# water_counter.net
KiCad netlist of a schematic drawn in EasyEDA
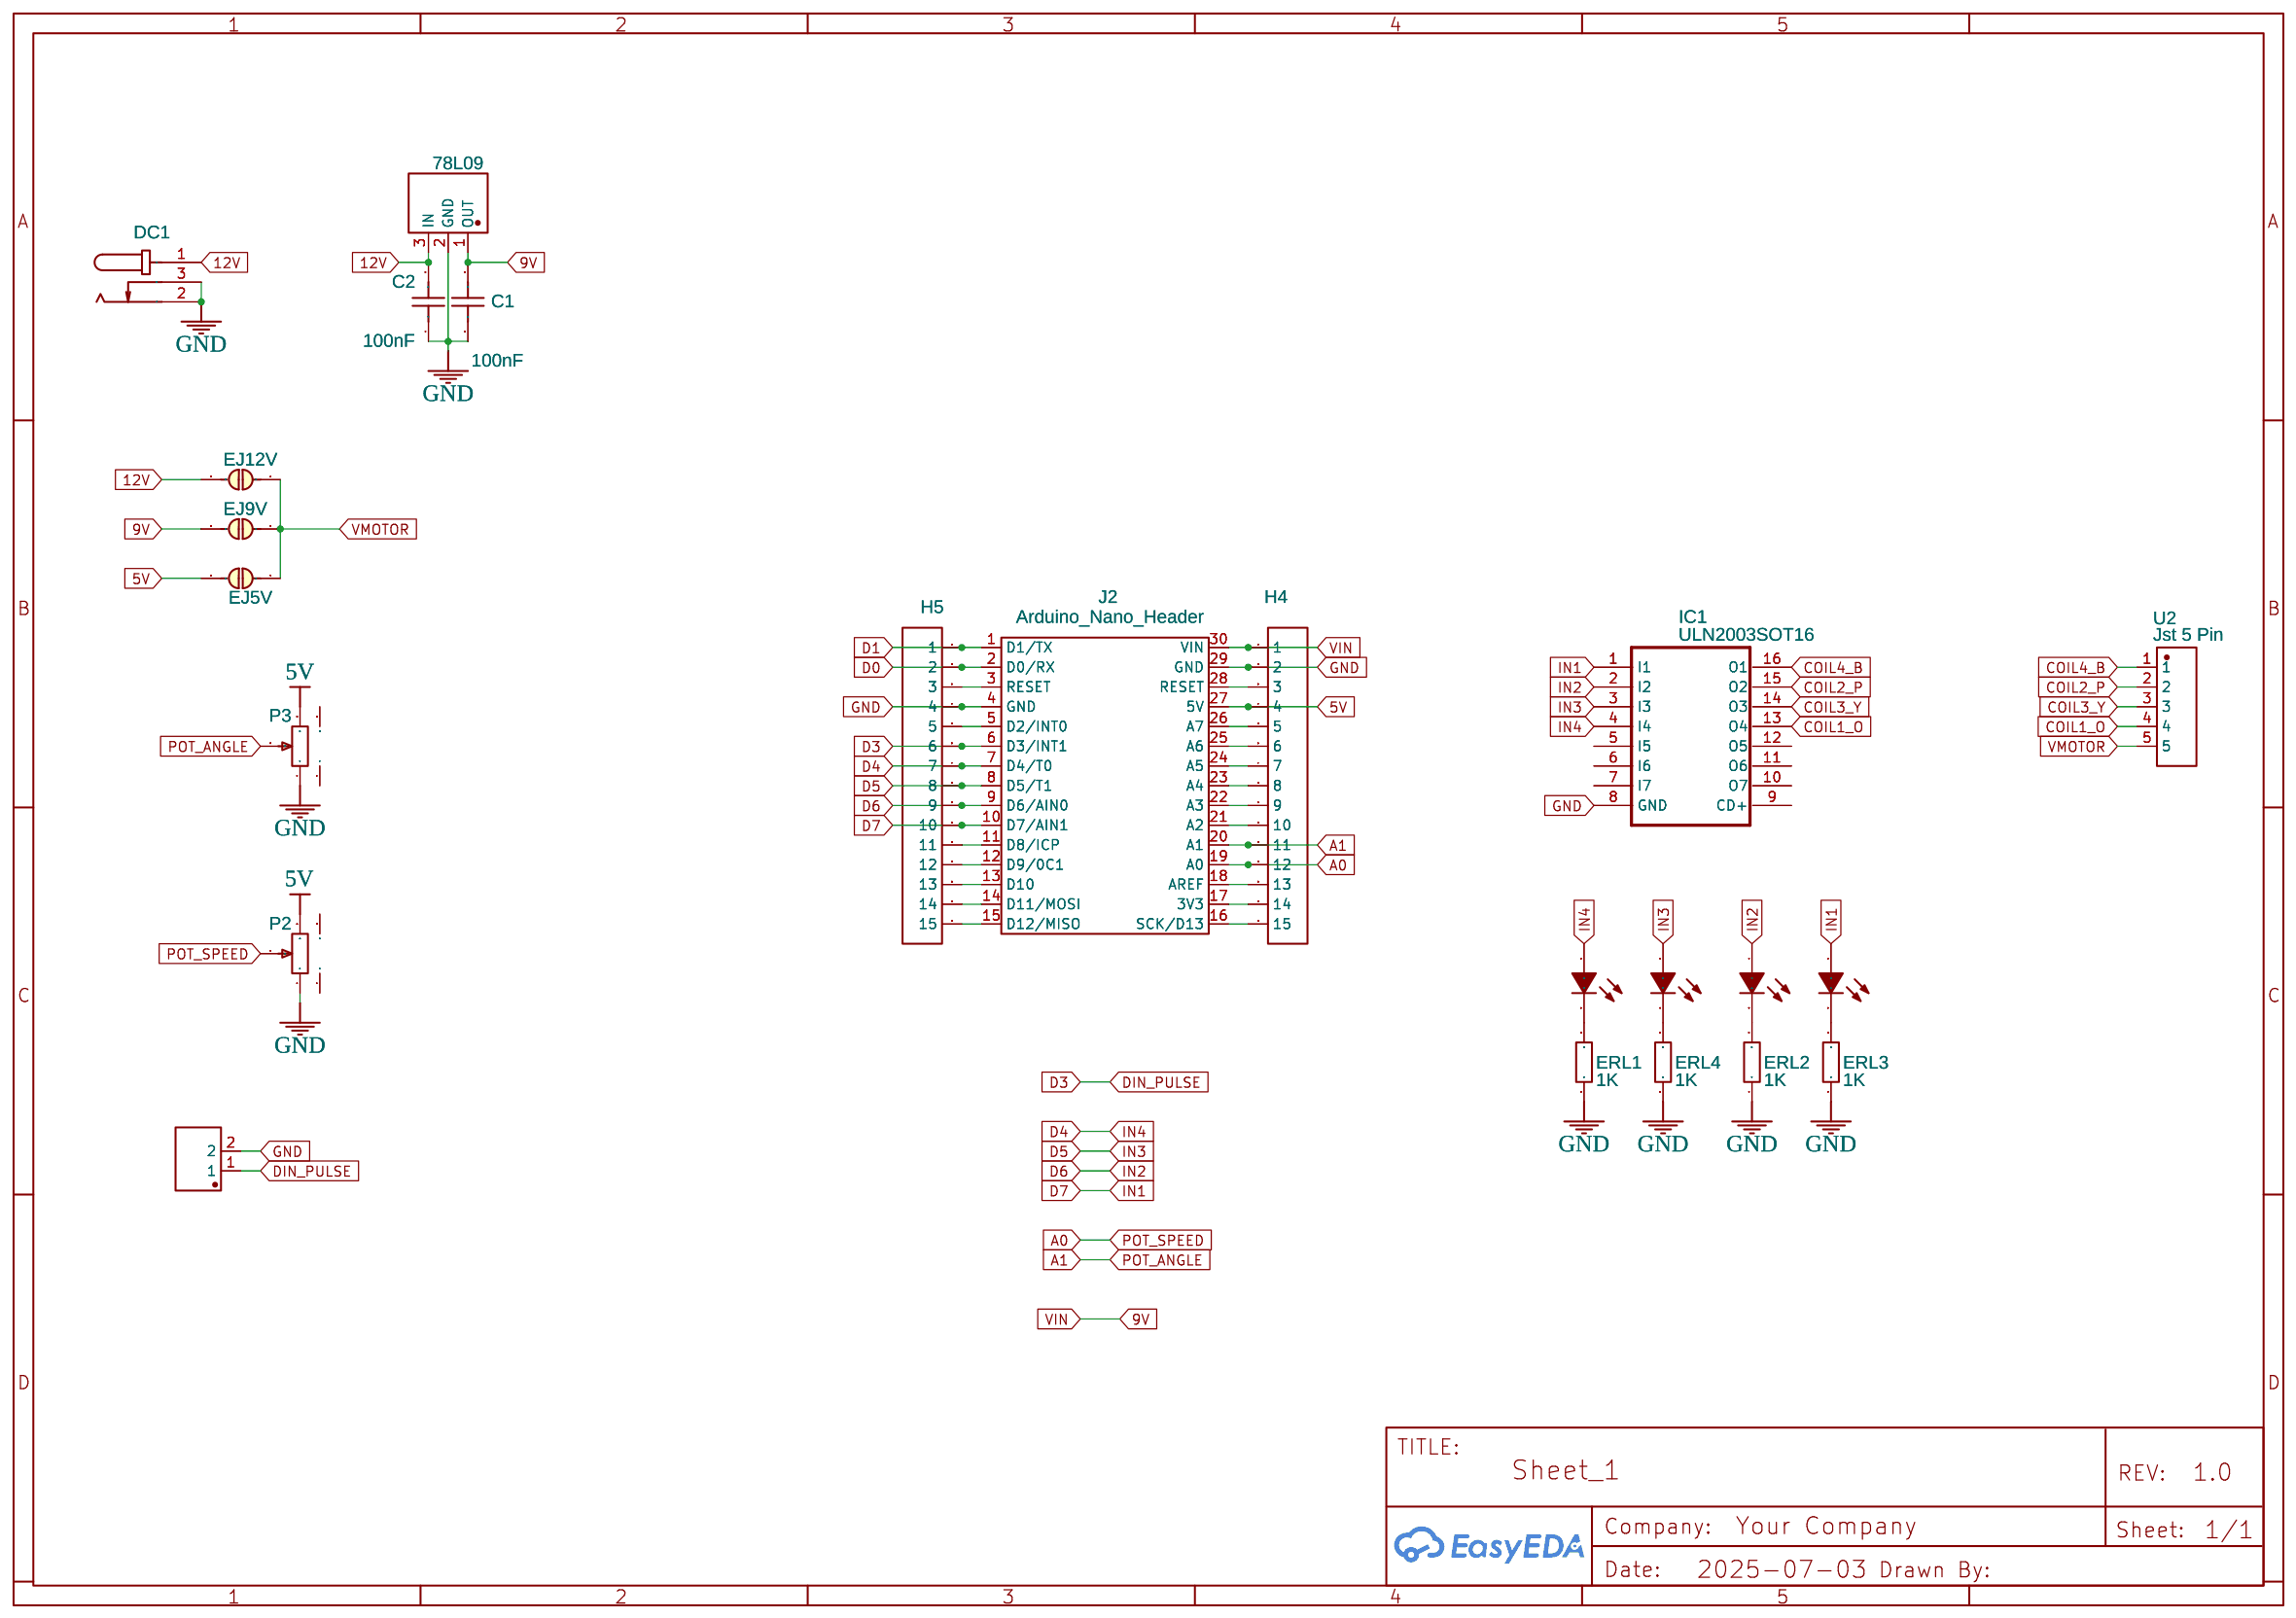
[diagram p0: schematic sheet]

(export (version "E")
  (design (tool "Eeschema 10.0.6"))
  (components
    (comp (ref "C1") (value "100nF") (libsource (lib "") (part "CC0603KRX7R9BB104")))
    (comp (ref "C2") (value "100nF") (libsource (lib "") (part "CC0603KRX7R9BB104")))
    (comp (ref "DC1")
      (value "DC")
      (fields (field (name "Manufacturer Part") "DC005-2.0MM") (field (name "Manufacturer") "SOFNG"))
      (libsource (lib "") (part "DC005-2.0MM"))
    )
    (comp (ref "EJ5V") (value "JUMPER-SMT_2") (libsource (lib "") (part "JUMPER-SMT_2_2")))
    (comp (ref "EJ9V") (value "JUMPER-SMT_2") (libsource (lib "") (part "JUMPER-SMT_2")))
    (comp (ref "EJ12V") (value "JUMPER-SMT_2") (libsource (lib "") (part "JUMPER-SMT_2_1")))
    (comp (ref "ELD1")
      (value "LED")
      (fields
        (field (name "Manufacturer Part") "19-217/BHC-ZL1M2RY/3T")
        (field (name "Manufacturer") "EVERLIGHT")
      )
      (libsource (lib "") (part "19-217/BHC-ZL1M2RY/3T"))
    )
    (comp (ref "ELD2")
      (value "LED")
      (fields
        (field (name "Manufacturer Part") "19-217/BHC-ZL1M2RY/3T")
        (field (name "Manufacturer") "EVERLIGHT")
      )
      (libsource (lib "") (part "19-217/BHC-ZL1M2RY/3T"))
    )
    (comp (ref "ELD3")
      (value "LED")
      (fields
        (field (name "Manufacturer Part") "19-217/BHC-ZL1M2RY/3T")
        (field (name "Manufacturer") "EVERLIGHT")
      )
      (libsource (lib "") (part "19-217/BHC-ZL1M2RY/3T"))
    )
    (comp (ref "ELD4")
      (value "LED")
      (fields
        (field (name "Manufacturer Part") "19-217/BHC-ZL1M2RY/3T")
        (field (name "Manufacturer") "EVERLIGHT")
      )
      (libsource (lib "") (part "19-217/BHC-ZL1M2RY/3T"))
    )
    (comp (ref "ERL1")
      (value "1K")
      (fields (field (name "Manufacturer Part") "0603WAF1001T5E") (field (name "Manufacturer") "UniOhm"))
      (libsource (lib "") (part "0603WAF1001T5E"))
    )
    (comp (ref "ERL2")
      (value "1K")
      (fields (field (name "Manufacturer Part") "0603WAF1001T5E") (field (name "Manufacturer") "UniOhm"))
      (libsource (lib "") (part "0603WAF1001T5E"))
    )
    (comp (ref "ERL3")
      (value "1K")
      (fields (field (name "Manufacturer Part") "0603WAF1001T5E") (field (name "Manufacturer") "UniOhm"))
      (libsource (lib "") (part "0603WAF1001T5E"))
    )
    (comp (ref "ERL4")
      (value "1K")
      (fields (field (name "Manufacturer Part") "0603WAF1001T5E") (field (name "Manufacturer") "UniOhm"))
      (libsource (lib "") (part "0603WAF1001T5E"))
    )
    (comp (ref "H4") (value "HDR-F-2.54_1x15") (libsource (lib "") (part "HDR-F-2.54_1x15_1")))
    (comp (ref "H5") (value "HDR-F-2.54_1x15") (libsource (lib "") (part "HDR-F-2.54_1x15")))
    (comp (ref "IC1") (value "ULN2003SOT16") (libsource (lib "") (part "ULN2003SOT16")))
    (comp (ref "J2") (value "Arduino_Nano_Header") (libsource (lib "") (part "Arduino_Nano_Header")))
    (comp (ref "OUT_11")
      (value "KF2510-2A")
      (fields (field (name "Manufacturer") "BOOMELE"))
      (libsource (lib "") (part "KF2510-2A"))
    )
    (comp (ref "P2") (value "长柄旋转电位器") (libsource (lib "") (part "长柄旋转电位器")))
    (comp (ref "P3") (value "长柄旋转电位器") (libsource (lib "") (part "长柄旋转电位器")))
    (comp (ref "U1")
      (value "78L09")
      (fields (field (name "Manufacturer") "CBI(创基)"))
      (libsource (lib "") (part "78L09U 78L09"))
    )
    (comp (ref "U2")
      (value "Jst 5 Pin")
      (fields (field (name "Manufacturer") "Vicky"))
      (libsource (lib "") (part "Jst 5 Pin"))
    )
  )
  (nets
    (net (code "1") (name "5V") (class "Default")
      (node (ref "EJ5V") (pin "2") (pinfunction "2_2") (pintype "bidirectional"))
      (node (ref "H4") (pin "4") (pinfunction "4_4") (pintype "unspecified"))
      (node (ref "J2") (pin "27") (pinfunction "5V_27") (pintype "unspecified"))
      (node (ref "P2") (pin "3") (pinfunction "3_3") (pintype "input"))
      (node (ref "P3") (pin "3") (pinfunction "3_3") (pintype "input"))
    )
    (net (code "2") (name "9V") (class "Default")
      (node (ref "C1") (pin "2") (pinfunction "2_2") (pintype "unspecified"))
      (node (ref "EJ9V") (pin "2") (pinfunction "2_2") (pintype "bidirectional"))
      (node (ref "H4") (pin "1") (pinfunction "1_1") (pintype "unspecified"))
      (node (ref "J2") (pin "30") (pinfunction "VIN_30") (pintype "unspecified"))
      (node (ref "U1") (pin "1") (pinfunction "OUT_1") (pintype "unspecified"))
    )
    (net (code "3") (name "12V") (class "Default")
      (node (ref "C2") (pin "2") (pinfunction "2_2") (pintype "unspecified"))
      (node (ref "DC1") (pin "1") (pinfunction "1_1") (pintype "unspecified"))
      (node (ref "EJ12V") (pin "2") (pinfunction "2_2") (pintype "bidirectional"))
      (node (ref "U1") (pin "3") (pinfunction "IN_3") (pintype "unspecified"))
    )
    (net (code "4") (name "A0") (class "Default")
      (node (ref "H4") (pin "12") (pinfunction "12_12") (pintype "unspecified"))
      (node (ref "J2") (pin "19") (pinfunction "A0_19") (pintype "unspecified"))
      (node (ref "P2") (pin "2") (pinfunction "2_2") (pintype "input"))
    )
    (net (code "5") (name "A1") (class "Default")
      (node (ref "H4") (pin "11") (pinfunction "11_11") (pintype "unspecified"))
      (node (ref "J2") (pin "20") (pinfunction "A1_20") (pintype "unspecified"))
      (node (ref "P3") (pin "2") (pinfunction "2_2") (pintype "input"))
    )
    (net (code "6") (name "COIL1_O") (class "Default")
      (node (ref "IC1") (pin "13") (pinfunction "O4_13") (pintype "bidirectional"))
      (node (ref "U2") (pin "4") (pinfunction "4_4") (pintype "unspecified"))
    )
    (net (code "7") (name "COIL2_P") (class "Default")
      (node (ref "IC1") (pin "15") (pinfunction "O2_15") (pintype "bidirectional"))
      (node (ref "U2") (pin "2") (pinfunction "2_2") (pintype "unspecified"))
    )
    (net (code "8") (name "COIL3_Y") (class "Default")
      (node (ref "IC1") (pin "14") (pinfunction "O3_14") (pintype "bidirectional"))
      (node (ref "U2") (pin "3") (pinfunction "3_3") (pintype "unspecified"))
    )
    (net (code "9") (name "COIL4_B") (class "Default")
      (node (ref "IC1") (pin "16") (pinfunction "O1_16") (pintype "bidirectional"))
      (node (ref "U2") (pin "1") (pinfunction "1_1") (pintype "unspecified"))
    )
    (net (code "10") (name "D0") (class "Default")
      (node (ref "H5") (pin "2") (pinfunction "2_2") (pintype "unspecified"))
      (node (ref "J2") (pin "2") (pinfunction "D0/RX_2") (pintype "unspecified"))
    )
    (net (code "11") (name "D1") (class "Default")
      (node (ref "H5") (pin "1") (pinfunction "1_1") (pintype "unspecified"))
      (node (ref "J2") (pin "1") (pinfunction "D1/TX_1") (pintype "unspecified"))
    )
    (net (code "12") (name "D3") (class "Default")
      (node (ref "H5") (pin "6") (pinfunction "6_6") (pintype "unspecified"))
      (node (ref "J2") (pin "6") (pinfunction "D3/INT1_6") (pintype "unspecified"))
      (node (ref "OUT_11") (pin "1") (pinfunction "1_1") (pintype "unspecified"))
    )
    (net (code "13") (name "D4") (class "Default")
      (node (ref "ELD1") (pin "1") (pinfunction "A_1") (pintype "input"))
      (node (ref "H5") (pin "7") (pinfunction "7_7") (pintype "unspecified"))
      (node (ref "IC1") (pin "4") (pinfunction "I4_4") (pintype "bidirectional"))
      (node (ref "J2") (pin "7") (pinfunction "D4/T0_7") (pintype "unspecified"))
    )
    (net (code "14") (name "D5") (class "Default")
      (node (ref "ELD4") (pin "1") (pinfunction "A_1") (pintype "input"))
      (node (ref "H5") (pin "8") (pinfunction "8_8") (pintype "unspecified"))
      (node (ref "IC1") (pin "3") (pinfunction "I3_3") (pintype "bidirectional"))
      (node (ref "J2") (pin "8") (pinfunction "D5/T1_8") (pintype "unspecified"))
    )
    (net (code "15") (name "D6") (class "Default")
      (node (ref "ELD2") (pin "1") (pinfunction "A_1") (pintype "input"))
      (node (ref "H5") (pin "9") (pinfunction "9_9") (pintype "unspecified"))
      (node (ref "IC1") (pin "2") (pinfunction "I2_2") (pintype "bidirectional"))
      (node (ref "J2") (pin "9") (pinfunction "D6/AIN0_9") (pintype "unspecified"))
    )
    (net (code "16") (name "D7") (class "Default")
      (node (ref "ELD3") (pin "1") (pinfunction "A_1") (pintype "input"))
      (node (ref "H5") (pin "10") (pinfunction "10_10") (pintype "unspecified"))
      (node (ref "IC1") (pin "1") (pinfunction "I1_1") (pintype "bidirectional"))
      (node (ref "J2") (pin "10") (pinfunction "D7/AIN1_10") (pintype "unspecified"))
    )
    (net (code "17") (name "GND") (class "Default")
      (node (ref "C1") (pin "1") (pinfunction "1_1") (pintype "unspecified"))
      (node (ref "C2") (pin "1") (pinfunction "1_1") (pintype "unspecified"))
      (node (ref "DC1") (pin "2") (pinfunction "2_2") (pintype "unspecified"))
      (node (ref "DC1") (pin "3") (pinfunction "3_3") (pintype "unspecified"))
      (node (ref "ERL1") (pin "1") (pinfunction "1_1") (pintype "input"))
      (node (ref "ERL2") (pin "1") (pinfunction "1_1") (pintype "input"))
      (node (ref "ERL3") (pin "1") (pinfunction "1_1") (pintype "input"))
      (node (ref "ERL4") (pin "1") (pinfunction "1_1") (pintype "input"))
      (node (ref "H4") (pin "2") (pinfunction "2_2") (pintype "unspecified"))
      (node (ref "H5") (pin "4") (pinfunction "4_4") (pintype "unspecified"))
      (node (ref "IC1") (pin "8") (pinfunction "GND_8") (pintype "bidirectional"))
      (node (ref "J2") (pin "29") (pinfunction "GND_29") (pintype "unspecified"))
      (node (ref "J2") (pin "4") (pinfunction "GND_4") (pintype "unspecified"))
      (node (ref "OUT_11") (pin "2") (pinfunction "2_2") (pintype "unspecified"))
      (node (ref "P2") (pin "1") (pinfunction "1_1") (pintype "input"))
      (node (ref "P3") (pin "1") (pinfunction "1_1") (pintype "input"))
      (node (ref "U1") (pin "2") (pinfunction "GND_2") (pintype "unspecified"))
    )
    (net (code "18") (name "Net-(ELD1-C)") (class "Default")
      (node (ref "ELD1") (pin "2") (pinfunction "C_2") (pintype "input"))
      (node (ref "ERL1") (pin "2") (pinfunction "2_2") (pintype "input"))
    )
    (net (code "19") (name "Net-(ELD2-C)") (class "Default")
      (node (ref "ELD2") (pin "2") (pinfunction "C_2") (pintype "input"))
      (node (ref "ERL2") (pin "2") (pinfunction "2_2") (pintype "input"))
    )
    (net (code "20") (name "Net-(ELD3-C)") (class "Default")
      (node (ref "ELD3") (pin "2") (pinfunction "C_2") (pintype "input"))
      (node (ref "ERL3") (pin "2") (pinfunction "2_2") (pintype "input"))
    )
    (net (code "21") (name "Net-(ELD4-C)") (class "Default")
      (node (ref "ELD4") (pin "2") (pinfunction "C_2") (pintype "input"))
      (node (ref "ERL4") (pin "2") (pinfunction "2_2") (pintype "input"))
    )
    (net (code "22") (name "Net-(H4-Pad3)") (class "Default")
      (node (ref "H4") (pin "3") (pinfunction "3_3") (pintype "unspecified"))
      (node (ref "J2") (pin "28") (pinfunction "RESET_28") (pintype "unspecified"))
    )
    (net (code "23") (name "Net-(H5-Pad3)") (class "Default")
      (node (ref "H5") (pin "3") (pinfunction "3_3") (pintype "unspecified"))
      (node (ref "J2") (pin "3") (pinfunction "RESET_3") (pintype "unspecified"))
    )
    (net (code "24") (name "Net-(J2-3V3)") (class "Default")
      (node (ref "H4") (pin "14") (pinfunction "14_14") (pintype "unspecified"))
      (node (ref "J2") (pin "17") (pinfunction "3V3_17") (pintype "unspecified"))
    )
    (net (code "25") (name "Net-(J2-A2)") (class "Default")
      (node (ref "H4") (pin "10") (pinfunction "10_10") (pintype "unspecified"))
      (node (ref "J2") (pin "21") (pinfunction "A2_21") (pintype "unspecified"))
    )
    (net (code "26") (name "Net-(J2-A3)") (class "Default")
      (node (ref "H4") (pin "9") (pinfunction "9_9") (pintype "unspecified"))
      (node (ref "J2") (pin "22") (pinfunction "A3_22") (pintype "unspecified"))
    )
    (net (code "27") (name "Net-(J2-A4)") (class "Default")
      (node (ref "H4") (pin "8") (pinfunction "8_8") (pintype "unspecified"))
      (node (ref "J2") (pin "23") (pinfunction "A4_23") (pintype "unspecified"))
    )
    (net (code "28") (name "Net-(J2-A5)") (class "Default")
      (node (ref "H4") (pin "7") (pinfunction "7_7") (pintype "unspecified"))
      (node (ref "J2") (pin "24") (pinfunction "A5_24") (pintype "unspecified"))
    )
    (net (code "29") (name "Net-(J2-A6)") (class "Default")
      (node (ref "H4") (pin "6") (pinfunction "6_6") (pintype "unspecified"))
      (node (ref "J2") (pin "25") (pinfunction "A6_25") (pintype "unspecified"))
    )
    (net (code "30") (name "Net-(J2-A7)") (class "Default")
      (node (ref "H4") (pin "5") (pinfunction "5_5") (pintype "unspecified"))
      (node (ref "J2") (pin "26") (pinfunction "A7_26") (pintype "unspecified"))
    )
    (net (code "31") (name "Net-(J2-AREF)") (class "Default")
      (node (ref "H4") (pin "13") (pinfunction "13_13") (pintype "unspecified"))
      (node (ref "J2") (pin "18") (pinfunction "AREF_18") (pintype "unspecified"))
    )
    (net (code "32") (name "Net-(J2-D2{slash}INT0)") (class "Default")
      (node (ref "H5") (pin "5") (pinfunction "5_5") (pintype "unspecified"))
      (node (ref "J2") (pin "5") (pinfunction "D2/INT0_5") (pintype "unspecified"))
    )
    (net (code "33") (name "Net-(J2-D8{slash}ICP)") (class "Default")
      (node (ref "H5") (pin "11") (pinfunction "11_11") (pintype "unspecified"))
      (node (ref "J2") (pin "11") (pinfunction "D8/ICP_11") (pintype "unspecified"))
    )
    (net (code "34") (name "Net-(J2-D9{slash}0C1)") (class "Default")
      (node (ref "H5") (pin "12") (pinfunction "12_12") (pintype "unspecified"))
      (node (ref "J2") (pin "12") (pinfunction "D9/0C1_12") (pintype "unspecified"))
    )
    (net (code "35") (name "Net-(J2-D10)") (class "Default")
      (node (ref "H5") (pin "13") (pinfunction "13_13") (pintype "unspecified"))
      (node (ref "J2") (pin "13") (pinfunction "D10_13") (pintype "unspecified"))
    )
    (net (code "36") (name "Net-(J2-D11{slash}MOSI)") (class "Default")
      (node (ref "H5") (pin "14") (pinfunction "14_14") (pintype "unspecified"))
      (node (ref "J2") (pin "14") (pinfunction "D11/MOSI_14") (pintype "unspecified"))
    )
    (net (code "37") (name "Net-(J2-D12{slash}MISO)") (class "Default")
      (node (ref "H5") (pin "15") (pinfunction "15_15") (pintype "unspecified"))
      (node (ref "J2") (pin "15") (pinfunction "D12/MISO_15") (pintype "unspecified"))
    )
    (net (code "38") (name "Net-(J2-SCK{slash}D13)") (class "Default")
      (node (ref "H4") (pin "15") (pinfunction "15_15") (pintype "unspecified"))
      (node (ref "J2") (pin "16") (pinfunction "SCK/D13_16") (pintype "unspecified"))
    )
    (net (code "39") (name "VMOTOR") (class "Default")
      (node (ref "EJ12V") (pin "1") (pinfunction "1_1") (pintype "bidirectional"))
      (node (ref "EJ5V") (pin "1") (pinfunction "1_1") (pintype "bidirectional"))
      (node (ref "EJ9V") (pin "1") (pinfunction "1_1") (pintype "bidirectional"))
      (node (ref "U2") (pin "5") (pinfunction "5_5") (pintype "unspecified"))
    )
    (net (code "40") (name "unconnected-(IC1-CD+-Pad9)") (class "Default")
      (node (ref "IC1") (pin "9") (pinfunction "CD+_9") (pintype "bidirectional"))
    )
    (net (code "41") (name "unconnected-(IC1-I5-Pad5)") (class "Default")
      (node (ref "IC1") (pin "5") (pinfunction "I5_5") (pintype "bidirectional"))
    )
    (net (code "42") (name "unconnected-(IC1-I6-Pad6)") (class "Default")
      (node (ref "IC1") (pin "6") (pinfunction "I6_6") (pintype "bidirectional"))
    )
    (net (code "43") (name "unconnected-(IC1-I7-Pad7)") (class "Default")
      (node (ref "IC1") (pin "7") (pinfunction "I7_7") (pintype "bidirectional"))
    )
    (net (code "44") (name "unconnected-(IC1-O5-Pad12)") (class "Default")
      (node (ref "IC1") (pin "12") (pinfunction "O5_12") (pintype "bidirectional"))
    )
    (net (code "45") (name "unconnected-(IC1-O6-Pad11)") (class "Default")
      (node (ref "IC1") (pin "11") (pinfunction "O6_11") (pintype "bidirectional"))
    )
    (net (code "46") (name "unconnected-(IC1-O7-Pad10)") (class "Default")
      (node (ref "IC1") (pin "10") (pinfunction "O7_10") (pintype "bidirectional"))
    )
    (net (code "47") (name "unconnected-(P2-Pad4)") (class "Default")
      (node (ref "P2") (pin "4") (pinfunction "4_4") (pintype "input"))
    )
    (net (code "48") (name "unconnected-(P2-Pad5)") (class "Default")
      (node (ref "P2") (pin "5") (pinfunction "5_5") (pintype "input"))
    )
    (net (code "49") (name "unconnected-(P3-Pad4)") (class "Default")
      (node (ref "P3") (pin "4") (pinfunction "4_4") (pintype "input"))
    )
    (net (code "50") (name "unconnected-(P3-Pad5)") (class "Default")
      (node (ref "P3") (pin "5") (pinfunction "5_5") (pintype "input"))
    )
  )
)
